# 485_232.net
KiCad netlist of a schematic drawn in Altium Designer
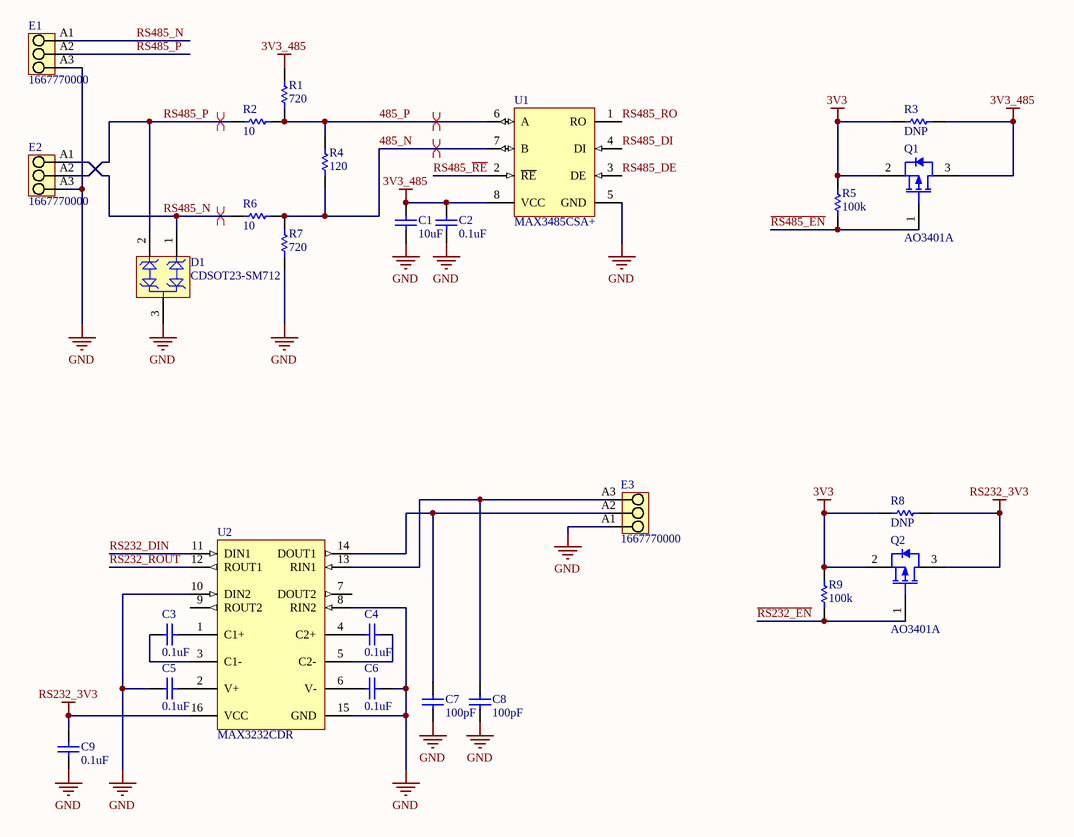
[diagram p0: 485&232.SchDoc]

(export (version "E")
  (design (tool "Eeschema 10.0.6"))
  (components
    (comp (ref "C1")
      (value "10uF")
      (footprint "CAPC0805(2012)145_L")
      (description "0805 (2012 Metric) Chip Capacitor")
      (libsource (lib "IC0") (part "CAP_5_1"))
    )
    (comp (ref "C2")
      (value "0.1uF")
      (footprint "CAPC0603(1608)100_L")
      (description "0603 (1608 Metric) Chip Capacitor")
      (libsource (lib "IC0") (part "CAP_5"))
    )
    (comp (ref "C3")
      (value "0.1uF")
      (footprint "CAPC0603(1608)100_L")
      (description "0603 (1608 Metric) Chip Capacitor")
      (libsource (lib "PCB_Project1") (part "CAP_5"))
    )
    (comp (ref "C4")
      (value "0.1uF")
      (footprint "CAPC0603(1608)100_L")
      (description "0603 (1608 Metric) Chip Capacitor")
      (libsource (lib "PCB_Project1") (part "CAP_5"))
    )
    (comp (ref "C5")
      (value "0.1uF")
      (footprint "CAPC0603(1608)100_L")
      (description "0603 (1608 Metric) Chip Capacitor")
      (libsource (lib "PCB_Project1") (part "CAP_5"))
    )
    (comp (ref "C6")
      (value "0.1uF")
      (footprint "CAPC0603(1608)100_L")
      (description "0603 (1608 Metric) Chip Capacitor")
      (libsource (lib "PCB_Project1") (part "CAP_5"))
    )
    (comp (ref "C7")
      (value "100pF")
      (footprint "CAPC0603(1608)100_L")
      (description "0603 (1608 Metric) Chip Capacitor")
      (libsource (lib "Altium Content Vault") (part "CAP_5"))
    )
    (comp (ref "C8")
      (value "100pF")
      (footprint "CAPC0603(1608)100_L")
      (description "0603 (1608 Metric) Chip Capacitor")
      (libsource (lib "Altium Content Vault") (part "CAP_5"))
    )
    (comp (ref "C9")
      (value "0.1uF")
      (footprint "CAPC0603(1608)100_L")
      (description "0603 (1608 Metric) Chip Capacitor")
      (libsource (lib "PCB_Project1") (part "CAP_5"))
    )
    (comp (ref "D1")
      (value "CDSOT23-SM712")
      (footprint "BOUR-SOT23-3_V")
      (description "Surface Mount TVS Diode, 17 A Ipp, -55 to 150 degC, 3-Pin SOT23, RoHS, Tape and Reel")
      (fields (field (name "MANUFACTURER") "Bourns"))
      (libsource (lib "Altium Content Vault") (part "BOUR-TVS-3"))
    )
    (comp (ref "E1")
      (value "1667770000")
      (footprint "LM_3_5_90_03")
      (description "OMNIMATE Signal - series LM")
      (fields (field (name "MANUFACTURER") "Weidmueller"))
      (libsource (lib "Altium Content Vault") (part "Terminal_03_1x03"))
    )
    (comp (ref "E2")
      (value "1667770000")
      (footprint "LM_3_5_90_03")
      (description "OMNIMATE Signal - series LM")
      (fields (field (name "MANUFACTURER") "Weidmueller"))
      (libsource (lib "Altium Content Vault") (part "Terminal_03_1x03"))
    )
    (comp (ref "E3")
      (value "1667770000")
      (footprint "LM_3_5_90_03")
      (description "OMNIMATE Signal - series LM")
      (fields (field (name "MANUFACTURER") "Weidmueller"))
      (libsource (lib "") (part "Terminal_03_1x03_1"))
    )
    (comp (ref "Q1")
      (value "AO3401A")
      (footprint "AO-SOT-23-3L_V")
      (description "P-Channel MOSFET, 30 V, 4 A, -55 to 150 degC, 3-Pin SOT-23-3L, RoHS, Tape and Reel")
      (fields (field (name "MANUFACTURER") "Alpha and Omega"))
      (libsource (lib "Altium Content Vault") (part "PEMOS-GSD-3"))
    )
    (comp (ref "Q2")
      (value "AO3401A")
      (footprint "AO-SOT-23-3L_V")
      (description "P-Channel MOSFET, 30 V, 4 A, -55 to 150 degC, 3-Pin SOT-23-3L, RoHS, Tape and Reel")
      (fields (field (name "MANUFACTURER") "Alpha and Omega"))
      (libsource (lib "Altium Content Vault") (part "PEMOS-GSD-3"))
    )
    (comp (ref "R1")
      (value "720")
      (footprint "RESC0603(1608)_L")
      (description "0603 (1608 Metric) Chip Resistor")
      (libsource (lib "PCB_Project1") (part "RES_3_1"))
    )
    (comp (ref "R2")
      (value "10")
      (footprint "RESC0603(1608)_L")
      (description "0603 (1608 Metric) Chip Resistor")
      (libsource (lib "PCB_Project1") (part "RES_3_1"))
    )
    (comp (ref "R3")
      (value "DNP")
      (footprint "RESC0603(1608)_L")
      (description "0603 (1608 Metric) Chip Resistor")
      (libsource (lib "PCB_Project1") (part "RES_3_1"))
    )
    (comp (ref "R4")
      (value "120")
      (footprint "RESC0603(1608)_L")
      (description "0603 (1608 Metric) Chip Resistor")
      (libsource (lib "PCB_Project1") (part "RES_3_1"))
    )
    (comp (ref "R5")
      (value "100k")
      (footprint "RESC0603(1608)_L")
      (description "0603 (1608 Metric) Chip Resistor")
      (libsource (lib "PCB_Project1") (part "RES_3_1"))
    )
    (comp (ref "R6")
      (value "10")
      (footprint "RESC0603(1608)_L")
      (description "0603 (1608 Metric) Chip Resistor")
      (libsource (lib "PCB_Project1") (part "RES_3_1"))
    )
    (comp (ref "R7")
      (value "720")
      (footprint "RESC0603(1608)_L")
      (description "0603 (1608 Metric) Chip Resistor")
      (libsource (lib "PCB_Project1") (part "RES_3_1"))
    )
    (comp (ref "R8")
      (value "DNP")
      (footprint "RESC0603(1608)_L")
      (description "0603 (1608 Metric) Chip Resistor")
      (libsource (lib "PCB_Project1") (part "RES_3_1"))
    )
    (comp (ref "R9")
      (value "100k")
      (footprint "RESC0603(1608)_L")
      (description "0603 (1608 Metric) Chip Resistor")
      (libsource (lib "PCB_Project1") (part "RES_3_1"))
    )
    (comp (ref "U1")
      (value "MAX3485CSA+")
      (footprint "SOIC-8")
      (fields (field (name "MANUFACTURER") "Maxim"))
      (libsource (lib "小车") (part "MAXM-MAX485CSA+-8"))
    )
    (comp (ref "U2")
      (value "MAX3232CDR")
      (footprint "D0016A_L")
      (libsource (lib "IC0") (part "TI-MAX3232-SOIC_D-16"))
    )
  )
  (nets
    (net (code "1") (name "/485_N") (class "Default")
      (node (ref "R4") (pin "2") (pinfunction "2_2") (pintype "passive"))
      (node (ref "R6") (pin "2") (pinfunction "2_2") (pintype "passive"))
      (node (ref "R7") (pin "1") (pinfunction "1_1") (pintype "passive"))
      (node (ref "U1") (pin "7") (pinfunction "B_7") (pintype "bidirectional"))
    )
    (net (code "2") (name "/485_P") (class "Default")
      (node (ref "R1") (pin "2") (pinfunction "2_2") (pintype "passive"))
      (node (ref "R2") (pin "2") (pinfunction "2_2") (pintype "passive"))
      (node (ref "R4") (pin "1") (pinfunction "1_1") (pintype "passive"))
      (node (ref "U1") (pin "6") (pinfunction "A_6") (pintype "bidirectional"))
    )
    (net (code "3") (name "/RS232_DIN") (class "Default")
      (node (ref "U2") (pin "11") (pinfunction "DIN1_11") (pintype "input"))
    )
    (net (code "4") (name "/RS232_ROUT") (class "Default")
      (node (ref "U2") (pin "12") (pinfunction "ROUT1_12") (pintype "output"))
    )
    (net (code "5") (name "/RS485_DE") (class "Default")
      (node (ref "U1") (pin "3") (pinfunction "DE_3") (pintype "input"))
    )
    (net (code "6") (name "/RS485_DI") (class "Default")
      (node (ref "U1") (pin "4") (pinfunction "DI_4") (pintype "input"))
    )
    (net (code "7") (name "/RS485_N") (class "Default")
      (node (ref "D1") (pin "1") (pinfunction "1_1") (pintype "passive"))
      (node (ref "E1") (pin "A1") (pinfunction "A1_A1") (pintype "passive"))
      (node (ref "E2") (pin "A1") (pinfunction "A1_A1") (pintype "passive"))
      (node (ref "R6") (pin "1") (pinfunction "1_1") (pintype "passive"))
    )
    (net (code "8") (name "/RS485_P") (class "Default")
      (node (ref "D1") (pin "2") (pinfunction "2_2") (pintype "passive"))
      (node (ref "E1") (pin "A2") (pinfunction "A2_A2") (pintype "passive"))
      (node (ref "E2") (pin "A2") (pinfunction "A2_A2") (pintype "passive"))
      (node (ref "R2") (pin "1") (pinfunction "1_1") (pintype "passive"))
    )
    (net (code "9") (name "/RS485_RO") (class "Default")
      (node (ref "U1") (pin "1") (pinfunction "RO_1") (pintype "tri_state"))
    )
    (net (code "10") (name "/RS485_~{RE}") (class "Default")
      (node (ref "U1") (pin "2") (pinfunction "~{RE}_2") (pintype "input"))
    )
    (net (code "11") (name "/~{RS232_EN}") (class "Default")
      (node (ref "Q2") (pin "1") (pinfunction "GATE_1") (pintype "passive"))
      (node (ref "R9") (pin "2") (pinfunction "2_2") (pintype "passive"))
    )
    (net (code "12") (name "/~{RS485_EN}") (class "Default")
      (node (ref "Q1") (pin "1") (pinfunction "GATE_1") (pintype "passive"))
      (node (ref "R5") (pin "2") (pinfunction "2_2") (pintype "passive"))
    )
    (net (code "13") (name "3V3") (class "Default")
      (node (ref "Q1") (pin "2") (pinfunction "SOURCE_2") (pintype "passive"))
      (node (ref "Q2") (pin "2") (pinfunction "SOURCE_2") (pintype "passive"))
      (node (ref "R3") (pin "1") (pinfunction "1_1") (pintype "passive"))
      (node (ref "R5") (pin "1") (pinfunction "1_1") (pintype "passive"))
      (node (ref "R8") (pin "1") (pinfunction "1_1") (pintype "passive"))
      (node (ref "R9") (pin "1") (pinfunction "1_1") (pintype "passive"))
    )
    (net (code "14") (name "3V3_485") (class "Default")
      (node (ref "C1") (pin "2") (pinfunction "2_2") (pintype "passive"))
      (node (ref "C2") (pin "2") (pinfunction "2_2") (pintype "passive"))
      (node (ref "Q1") (pin "3") (pinfunction "DRAIN_3") (pintype "passive"))
      (node (ref "R1") (pin "1") (pinfunction "1_1") (pintype "passive"))
      (node (ref "R3") (pin "2") (pinfunction "2_2") (pintype "passive"))
      (node (ref "U1") (pin "8") (pinfunction "VCC_8") (pintype "power_in"))
    )
    (net (code "15") (name "GND") (class "Default")
      (node (ref "C1") (pin "1") (pinfunction "1_1") (pintype "passive"))
      (node (ref "C2") (pin "1") (pinfunction "1_1") (pintype "passive"))
      (node (ref "C5") (pin "2") (pinfunction "2_2") (pintype "passive"))
      (node (ref "C6") (pin "2") (pinfunction "2_2") (pintype "passive"))
      (node (ref "C7") (pin "1") (pinfunction "1_1") (pintype "passive"))
      (node (ref "C8") (pin "1") (pinfunction "1_1") (pintype "passive"))
      (node (ref "C9") (pin "1") (pinfunction "1_1") (pintype "passive"))
      (node (ref "D1") (pin "3") (pinfunction "3_3") (pintype "passive"))
      (node (ref "E1") (pin "A3") (pinfunction "A3_A3") (pintype "passive"))
      (node (ref "E2") (pin "A3") (pinfunction "A3_A3") (pintype "passive"))
      (node (ref "E3") (pin "A1") (pinfunction "A1_A1") (pintype "passive"))
      (node (ref "R7") (pin "2") (pinfunction "2_2") (pintype "passive"))
      (node (ref "U1") (pin "5") (pinfunction "GND_5") (pintype "power_in"))
      (node (ref "U2") (pin "10") (pinfunction "DIN2_10") (pintype "input"))
      (node (ref "U2") (pin "15") (pinfunction "GND_15") (pintype "power_in"))
      (node (ref "U2") (pin "8") (pinfunction "RIN2_8") (pintype "input"))
    )
    (net (code "16") (name "Net-(U2-C1+)") (class "Default")
      (node (ref "C3") (pin "1") (pinfunction "1_1") (pintype "passive"))
      (node (ref "U2") (pin "1") (pinfunction "C1+_1") (pintype "passive"))
    )
    (net (code "17") (name "Net-(U2-C1-)") (class "Default")
      (node (ref "C3") (pin "2") (pinfunction "2_2") (pintype "passive"))
      (node (ref "U2") (pin "3") (pinfunction "C1-_3") (pintype "passive"))
    )
    (net (code "18") (name "Net-(U2-C2+)") (class "Default")
      (node (ref "C4") (pin "2") (pinfunction "2_2") (pintype "passive"))
      (node (ref "U2") (pin "4") (pinfunction "C2+_4") (pintype "passive"))
    )
    (net (code "19") (name "Net-(U2-C2-)") (class "Default")
      (node (ref "C4") (pin "1") (pinfunction "1_1") (pintype "passive"))
      (node (ref "U2") (pin "5") (pinfunction "C2-_5") (pintype "passive"))
    )
    (net (code "20") (name "Net-(U2-DOUT1)") (class "Default")
      (node (ref "C7") (pin "2") (pinfunction "2_2") (pintype "passive"))
      (node (ref "E3") (pin "A2") (pinfunction "A2_A2") (pintype "passive"))
      (node (ref "U2") (pin "14") (pinfunction "DOUT1_14") (pintype "output"))
    )
    (net (code "21") (name "Net-(U2-RIN1)") (class "Default")
      (node (ref "C8") (pin "2") (pinfunction "2_2") (pintype "passive"))
      (node (ref "E3") (pin "A3") (pinfunction "A3_A3") (pintype "passive"))
      (node (ref "U2") (pin "13") (pinfunction "RIN1_13") (pintype "input"))
    )
    (net (code "22") (name "Net-(U2-V+)") (class "Default")
      (node (ref "C5") (pin "1") (pinfunction "1_1") (pintype "passive"))
      (node (ref "U2") (pin "2") (pinfunction "V+_2") (pintype "power_in"))
    )
    (net (code "23") (name "Net-(U2-V-)") (class "Default")
      (node (ref "C6") (pin "1") (pinfunction "1_1") (pintype "passive"))
      (node (ref "U2") (pin "6") (pinfunction "V-_6") (pintype "power_in"))
    )
    (net (code "24") (name "RS232_3V3") (class "Default")
      (node (ref "C9") (pin "2") (pinfunction "2_2") (pintype "passive"))
      (node (ref "Q2") (pin "3") (pinfunction "DRAIN_3") (pintype "passive"))
      (node (ref "R8") (pin "2") (pinfunction "2_2") (pintype "passive"))
      (node (ref "U2") (pin "16") (pinfunction "VCC_16") (pintype "power_in"))
    )
    (net (code "25") (name "unconnected-(U2-DOUT2-Pad7)") (class "Default")
      (node (ref "U2") (pin "7") (pinfunction "DOUT2_7") (pintype "output"))
    )
    (net (code "26") (name "unconnected-(U2-ROUT2-Pad9)") (class "Default")
      (node (ref "U2") (pin "9") (pinfunction "ROUT2_9") (pintype "output"))
    )
  )
)
